# logic_board.net
KiCad netlist of a schematic drawn in EAGLE
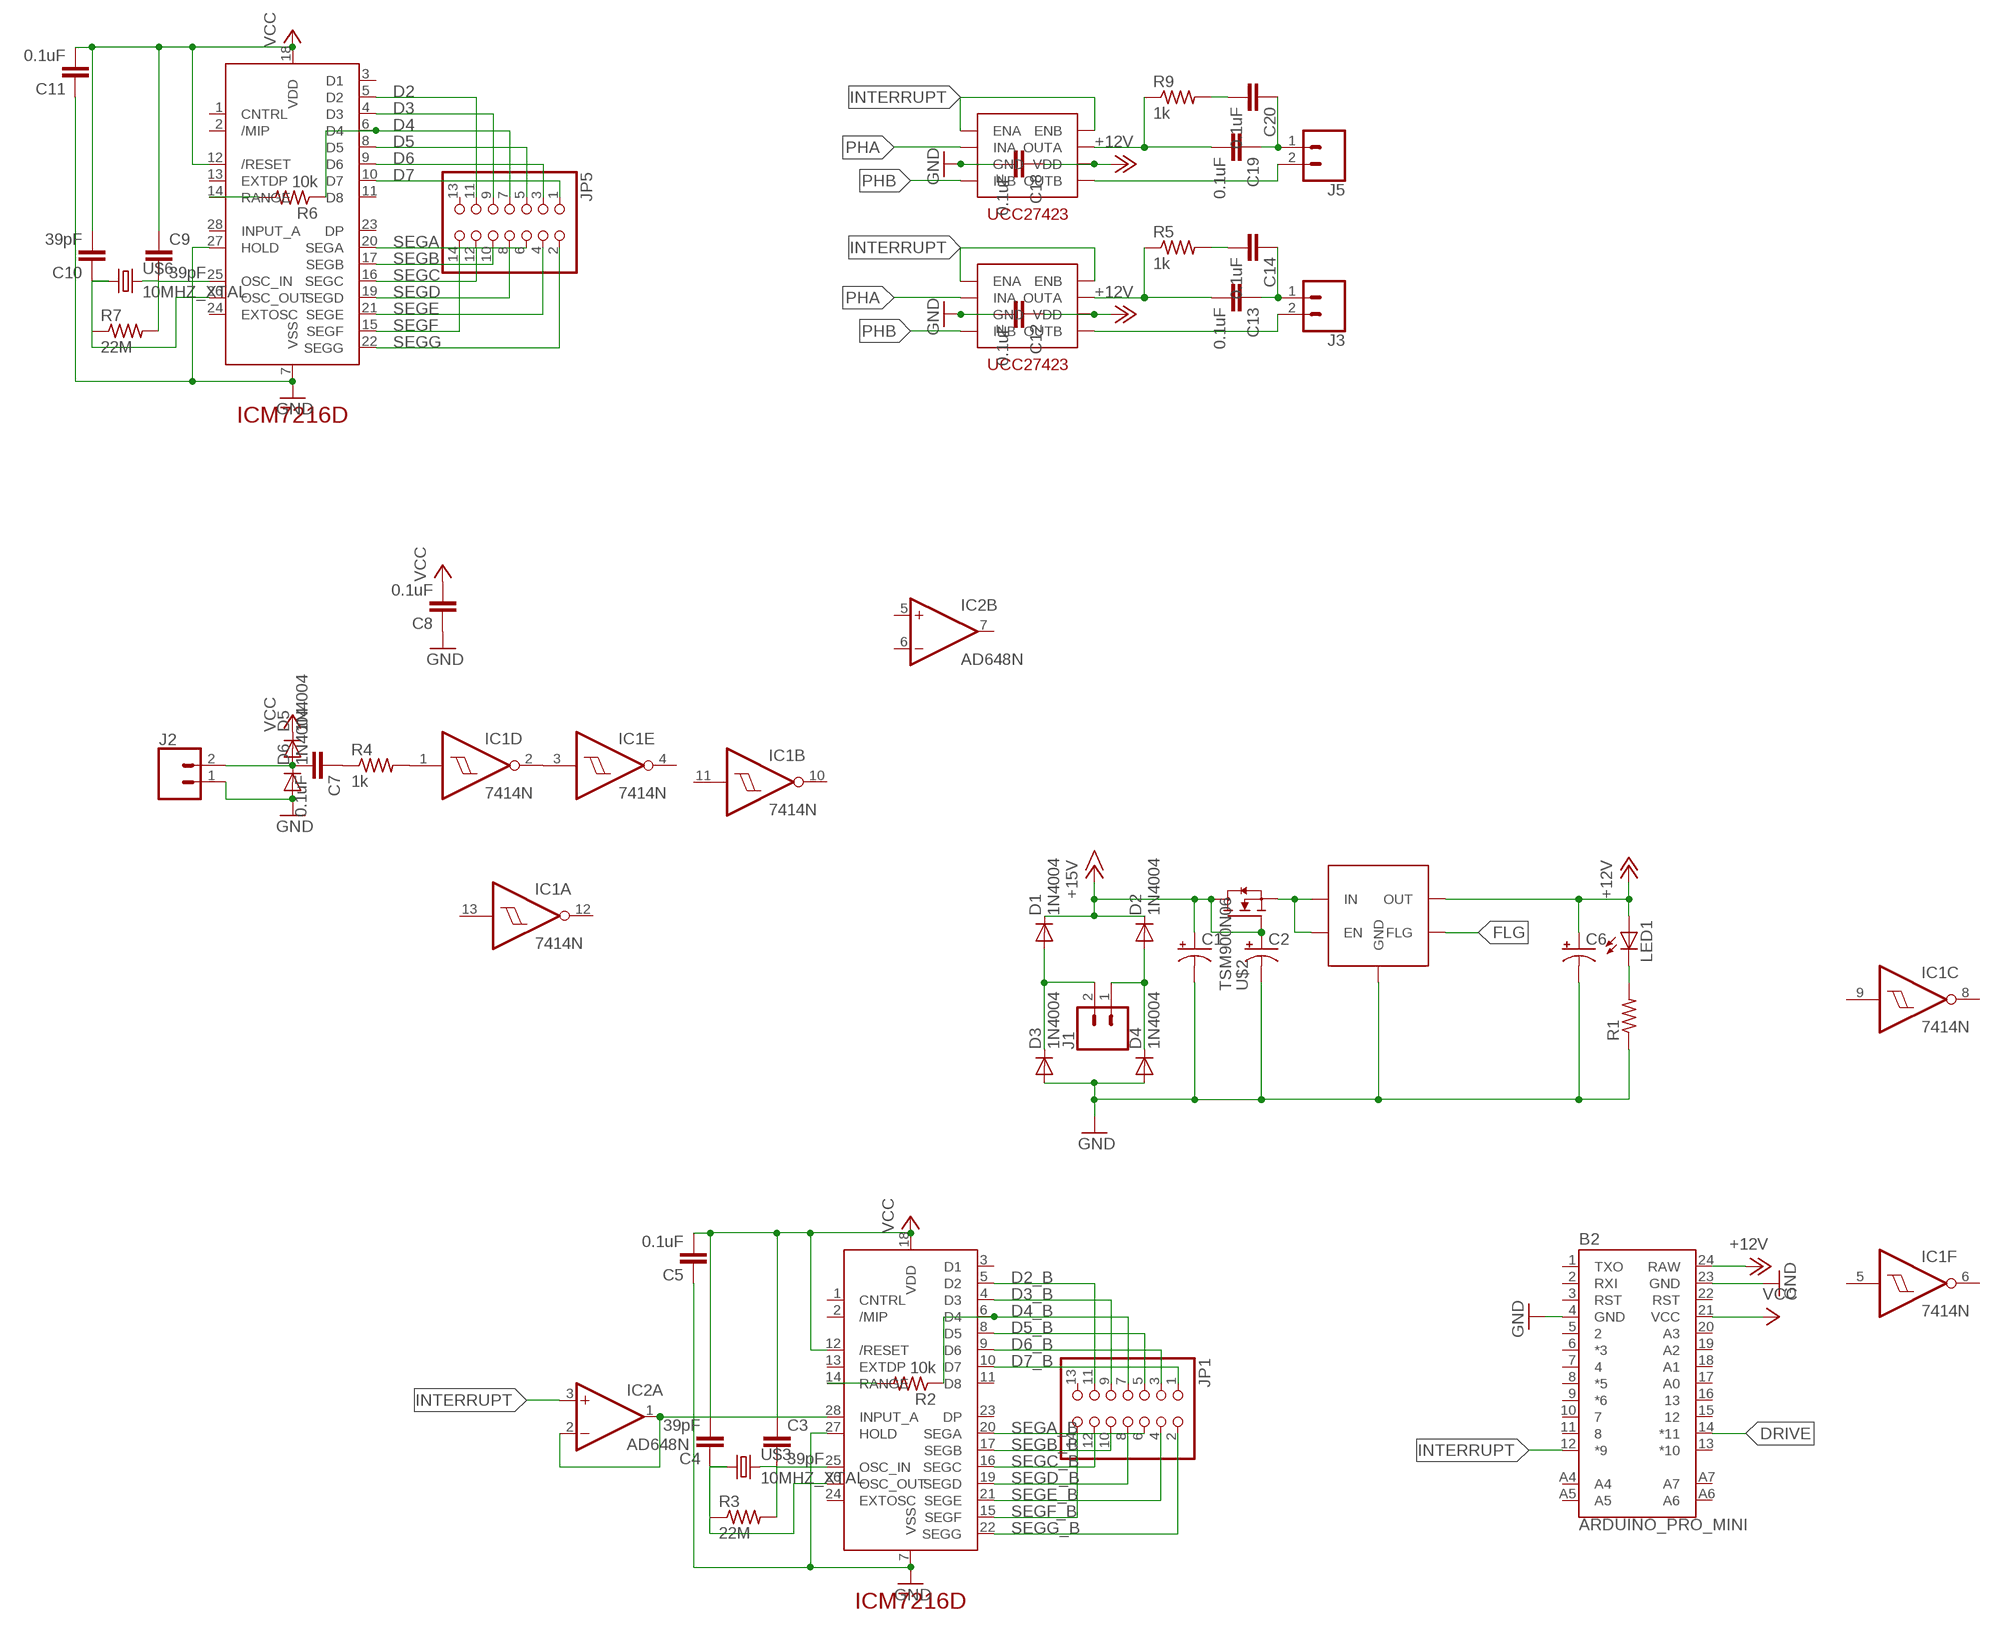
[diagram p0: schematic, sheet 1]

(export (version "E")
  (design (tool "Eeschema 10.0.6"))
  (components
    (comp (ref "B2")
      (value "ARDUINO_PRO_MINI")
      (footprint "eagle-import:ARDUINO_PRO_MINI")
      (libsource (lib "eagle-import") (part "ARDUINO_PRO_MINI"))
    )
    (comp (ref "C1")
      (value "CPOL-USE7.5-16")
      (footprint "eagle-import:E7,5-16")
      (libsource (lib "eagle-import") (part "CPOL-USE7.5-16"))
    )
    (comp (ref "C2")
      (value "CPOL-USE7.5-16")
      (footprint "eagle-import:E7,5-16")
      (libsource (lib "eagle-import") (part "CPOL-USE7.5-16"))
    )
    (comp (ref "C3")
      (value "39pF")
      (footprint "eagle-import:C050-030X075")
      (libsource (lib "eagle-import") (part "C-EU050-030X075"))
    )
    (comp (ref "C4")
      (value "39pF")
      (footprint "eagle-import:C050-030X075")
      (libsource (lib "eagle-import") (part "C-EU050-030X075"))
    )
    (comp (ref "C5")
      (value "0.1uF")
      (footprint "eagle-import:C050-030X075")
      (libsource (lib "eagle-import") (part "C-EU050-030X075"))
    )
    (comp (ref "C6")
      (value "CPOL-USE7.5-16")
      (footprint "eagle-import:E7,5-16")
      (libsource (lib "eagle-import") (part "CPOL-USE7.5-16"))
    )
    (comp (ref "C7")
      (value "0.1uF")
      (footprint "eagle-import:C050-030X075")
      (libsource (lib "eagle-import") (part "C-EU050-030X075"))
    )
    (comp (ref "C8")
      (value "0.1uF")
      (footprint "eagle-import:C050-030X075")
      (libsource (lib "eagle-import") (part "C-EU050-030X075"))
    )
    (comp (ref "C9")
      (value "39pF")
      (footprint "eagle-import:C050-030X075")
      (libsource (lib "eagle-import") (part "C-EU050-030X075"))
    )
    (comp (ref "C10")
      (value "39pF")
      (footprint "eagle-import:C050-030X075")
      (libsource (lib "eagle-import") (part "C-EU050-030X075"))
    )
    (comp (ref "C11")
      (value "0.1uF")
      (footprint "eagle-import:C050-030X075")
      (libsource (lib "eagle-import") (part "C-EU050-030X075"))
    )
    (comp (ref "C12")
      (value "0.1uF")
      (footprint "eagle-import:C050-030X075")
      (libsource (lib "eagle-import") (part "C-EU050-030X075"))
    )
    (comp (ref "C13")
      (value "0.1uF")
      (footprint "eagle-import:C050-030X075")
      (libsource (lib "eagle-import") (part "C-EU050-030X075"))
    )
    (comp (ref "C14")
      (value "0.1uF")
      (footprint "eagle-import:C050-030X075")
      (libsource (lib "eagle-import") (part "C-EU050-030X075"))
    )
    (comp (ref "C18")
      (value "0.1uF")
      (footprint "eagle-import:C050-030X075")
      (libsource (lib "eagle-import") (part "C-EU050-030X075"))
    )
    (comp (ref "C19")
      (value "0.1uF")
      (footprint "eagle-import:C050-030X075")
      (libsource (lib "eagle-import") (part "C-EU050-030X075"))
    )
    (comp (ref "C20")
      (value "0.1uF")
      (footprint "eagle-import:C050-030X075")
      (libsource (lib "eagle-import") (part "C-EU050-030X075"))
    )
    (comp (ref "D1")
      (value "1N4004")
      (footprint "eagle-import:DO41-10")
      (libsource (lib "eagle-import") (part "1N4004"))
    )
    (comp (ref "D2")
      (value "1N4004")
      (footprint "eagle-import:DO41-10")
      (libsource (lib "eagle-import") (part "1N4004"))
    )
    (comp (ref "D3")
      (value "1N4004")
      (footprint "eagle-import:DO41-10")
      (libsource (lib "eagle-import") (part "1N4004"))
    )
    (comp (ref "D4")
      (value "1N4004")
      (footprint "eagle-import:DO41-10")
      (libsource (lib "eagle-import") (part "1N4004"))
    )
    (comp (ref "D5")
      (value "1N4004")
      (footprint "eagle-import:DO41-10")
      (libsource (lib "eagle-import") (part "1N4004"))
    )
    (comp (ref "D6")
      (value "1N4004")
      (footprint "eagle-import:DO41-10")
      (libsource (lib "eagle-import") (part "1N4004"))
    )
    (comp (ref "IC1")
      (value "7414N")
      (footprint "eagle-import:DIL14")
      (libsource (lib "eagle-import") (part "7414N"))
    )
    (comp (ref "IC2")
      (value "AD648N")
      (footprint "eagle-import:DIL08")
      (libsource (lib "eagle-import") (part "AD648N"))
    )
    (comp (ref "J1")
      (value "CONN_025MM")
      (footprint "eagle-import:SCREWTERMINAL-5MM-2")
      (libsource (lib "eagle-import") (part "CONN_025MM"))
    )
    (comp (ref "J2")
      (value "CONN_025MM")
      (footprint "eagle-import:SCREWTERMINAL-5MM-2")
      (libsource (lib "eagle-import") (part "CONN_025MM"))
    )
    (comp (ref "J3")
      (value "CONN_025MM")
      (footprint "eagle-import:SCREWTERMINAL-5MM-2")
      (libsource (lib "eagle-import") (part "CONN_025MM"))
    )
    (comp (ref "J5")
      (value "CONN_025MM")
      (footprint "eagle-import:SCREWTERMINAL-5MM-2")
      (libsource (lib "eagle-import") (part "CONN_025MM"))
    )
    (comp (ref "JP1")
      (value "PINHD-2X7")
      (footprint "eagle-import:2X07")
      (libsource (lib "eagle-import") (part "PINHD-2X7"))
    )
    (comp (ref "JP5")
      (value "PINHD-2X7")
      (footprint "eagle-import:2X07")
      (libsource (lib "eagle-import") (part "PINHD-2X7"))
    )
    (comp (ref "LED1")
      (value "LED5MM")
      (footprint "eagle-import:LED5MM")
      (libsource (lib "eagle-import") (part "LED5MM"))
    )
    (comp (ref "R1")
      (value "R-US_0204/7")
      (footprint "eagle-import:0204_7")
      (libsource (lib "eagle-import") (part "R-US_0204/7"))
    )
    (comp (ref "R2")
      (value "10k")
      (footprint "eagle-import:0204_7")
      (libsource (lib "eagle-import") (part "R-US_0204/7"))
    )
    (comp (ref "R3")
      (value "22M")
      (footprint "eagle-import:0204_7")
      (libsource (lib "eagle-import") (part "R-US_0204/7"))
    )
    (comp (ref "R4")
      (value "1k")
      (footprint "eagle-import:0204_7")
      (libsource (lib "eagle-import") (part "R-US_0204/7"))
    )
    (comp (ref "R5")
      (value "1k")
      (footprint "eagle-import:0204_7")
      (libsource (lib "eagle-import") (part "R-US_0204/7"))
    )
    (comp (ref "R6")
      (value "10k")
      (footprint "eagle-import:0204_7")
      (libsource (lib "eagle-import") (part "R-US_0204/7"))
    )
    (comp (ref "R7")
      (value "22M")
      (footprint "eagle-import:0204_7")
      (libsource (lib "eagle-import") (part "R-US_0204/7"))
    )
    (comp (ref "R9")
      (value "1k")
      (footprint "eagle-import:0204_7")
      (libsource (lib "eagle-import") (part "R-US_0204/7"))
    )
    (comp (ref "U$1")
      (value "ICM7216D")
      (footprint "eagle-import:DIP1524W55P254L3740H635Q28B")
      (libsource (lib "eagle-import") (part "ICM7216D"))
    )
    (comp (ref "U$2")
      (value "TSM900N06")
      (footprint "eagle-import:TO-251S")
      (libsource (lib "eagle-import") (part "TSM900N06"))
    )
    (comp (ref "U$3")
      (value "10MHZ_XTAL")
      (footprint "eagle-import:XTAL")
      (libsource (lib "eagle-import") (part "10MHZ_XTAL"))
    )
    (comp (ref "U$4")
      (value "MIC29301")
      (footprint "eagle-import:TO-220")
      (libsource (lib "eagle-import") (part "MIC29301"))
    )
    (comp (ref "U$5")
      (value "ICM7216D")
      (footprint "eagle-import:DIP1524W55P254L3740H635Q28B")
      (libsource (lib "eagle-import") (part "ICM7216D"))
    )
    (comp (ref "U$6")
      (value "10MHZ_XTAL")
      (footprint "eagle-import:XTAL")
      (libsource (lib "eagle-import") (part "10MHZ_XTAL"))
    )
    (comp (ref "U$7")
      (value "UCC27423")
      (footprint "eagle-import:DIP762W53P254L959H508Q8B")
      (libsource (lib "eagle-import") (part "UCC27423"))
    )
    (comp (ref "U$9")
      (value "UCC27423")
      (footprint "eagle-import:DIP762W53P254L959H508Q8B")
      (libsource (lib "eagle-import") (part "UCC27423"))
    )
  )
  (nets
    (net (code "1") (name "+12V") (class "Default")
      (node (ref "B2") (pin "24") (pinfunction "RAW_24") (pintype "power_in"))
      (node (ref "C12") (pin "1") (pinfunction "1_1") (pintype "passive"))
      (node (ref "C18") (pin "1") (pinfunction "1_1") (pintype "passive"))
      (node (ref "C6") (pin "+") (pinfunction "+_+") (pintype "passive"))
      (node (ref "LED1") (pin "A") (pinfunction "A_A") (pintype "passive"))
      (node (ref "U$4") (pin "P$4") (pinfunction "OUT_P$4") (pintype "bidirectional"))
      (node (ref "U$7") (pin "6") (pinfunction "VDD_6") (pintype "bidirectional"))
      (node (ref "U$9") (pin "6") (pinfunction "VDD_6") (pintype "bidirectional"))
    )
    (net (code "2") (name "+15V") (class "Default")
      (node (ref "C1") (pin "+") (pinfunction "+_+") (pintype "passive"))
      (node (ref "C2") (pin "+") (pinfunction "+_+") (pintype "passive"))
      (node (ref "D1") (pin "C") (pinfunction "C_C") (pintype "passive"))
      (node (ref "D2") (pin "C") (pinfunction "C_C") (pintype "passive"))
      (node (ref "U$2") (pin "P$1") (pinfunction "G_P$1") (pintype "passive"))
      (node (ref "U$2") (pin "P$2") (pinfunction "D_P$2") (pintype "passive"))
    )
    (net (code "3") (name "/D2") (class "Default")
      (node (ref "JP5") (pin "11") (pinfunction "11_11") (pintype "passive"))
      (node (ref "U$5") (pin "5") (pinfunction "D2_5") (pintype "bidirectional"))
    )
    (net (code "4") (name "/D2_B") (class "Default")
      (node (ref "JP1") (pin "11") (pinfunction "11_11") (pintype "passive"))
      (node (ref "U$1") (pin "5") (pinfunction "D2_5") (pintype "bidirectional"))
    )
    (net (code "5") (name "/D3") (class "Default")
      (node (ref "JP5") (pin "9") (pinfunction "9_9") (pintype "passive"))
      (node (ref "U$5") (pin "4") (pinfunction "D3_4") (pintype "bidirectional"))
    )
    (net (code "6") (name "/D3_B") (class "Default")
      (node (ref "JP1") (pin "9") (pinfunction "9_9") (pintype "passive"))
      (node (ref "U$1") (pin "4") (pinfunction "D3_4") (pintype "bidirectional"))
    )
    (net (code "7") (name "/D4") (class "Default")
      (node (ref "JP5") (pin "7") (pinfunction "7_7") (pintype "passive"))
      (node (ref "R6") (pin "1") (pinfunction "1_1") (pintype "passive"))
      (node (ref "U$5") (pin "6") (pinfunction "D4_6") (pintype "bidirectional"))
    )
    (net (code "8") (name "/D4_B") (class "Default")
      (node (ref "JP1") (pin "7") (pinfunction "7_7") (pintype "passive"))
      (node (ref "R2") (pin "1") (pinfunction "1_1") (pintype "passive"))
      (node (ref "U$1") (pin "6") (pinfunction "D4_6") (pintype "bidirectional"))
    )
    (net (code "9") (name "/D5") (class "Default")
      (node (ref "JP5") (pin "5") (pinfunction "5_5") (pintype "passive"))
      (node (ref "U$5") (pin "8") (pinfunction "D5_8") (pintype "bidirectional"))
    )
    (net (code "10") (name "/D5_B") (class "Default")
      (node (ref "JP1") (pin "5") (pinfunction "5_5") (pintype "passive"))
      (node (ref "U$1") (pin "8") (pinfunction "D5_8") (pintype "bidirectional"))
    )
    (net (code "11") (name "/D6") (class "Default")
      (node (ref "JP5") (pin "3") (pinfunction "3_3") (pintype "passive"))
      (node (ref "U$5") (pin "9") (pinfunction "D6_9") (pintype "bidirectional"))
    )
    (net (code "12") (name "/D6_B") (class "Default")
      (node (ref "JP1") (pin "3") (pinfunction "3_3") (pintype "passive"))
      (node (ref "U$1") (pin "9") (pinfunction "D6_9") (pintype "bidirectional"))
    )
    (net (code "13") (name "/D7") (class "Default")
      (node (ref "JP5") (pin "1") (pinfunction "1_1") (pintype "passive"))
      (node (ref "U$5") (pin "10") (pinfunction "D7_10") (pintype "bidirectional"))
    )
    (net (code "14") (name "/D7_B") (class "Default")
      (node (ref "JP1") (pin "1") (pinfunction "1_1") (pintype "passive"))
      (node (ref "U$1") (pin "10") (pinfunction "D7_10") (pintype "bidirectional"))
    )
    (net (code "15") (name "/SEGA") (class "Default")
      (node (ref "JP5") (pin "6") (pinfunction "6_6") (pintype "passive"))
      (node (ref "U$5") (pin "20") (pinfunction "SEGA_20") (pintype "bidirectional"))
    )
    (net (code "16") (name "/SEGA_B") (class "Default")
      (node (ref "JP1") (pin "6") (pinfunction "6_6") (pintype "passive"))
      (node (ref "U$1") (pin "20") (pinfunction "SEGA_20") (pintype "bidirectional"))
    )
    (net (code "17") (name "/SEGB") (class "Default")
      (node (ref "JP5") (pin "10") (pinfunction "10_10") (pintype "passive"))
      (node (ref "U$5") (pin "17") (pinfunction "SEGB_17") (pintype "bidirectional"))
    )
    (net (code "18") (name "/SEGB_B") (class "Default")
      (node (ref "JP1") (pin "10") (pinfunction "10_10") (pintype "passive"))
      (node (ref "U$1") (pin "17") (pinfunction "SEGB_17") (pintype "bidirectional"))
    )
    (net (code "19") (name "/SEGC") (class "Default")
      (node (ref "JP5") (pin "12") (pinfunction "12_12") (pintype "passive"))
      (node (ref "U$5") (pin "16") (pinfunction "SEGC_16") (pintype "bidirectional"))
    )
    (net (code "20") (name "/SEGC_B") (class "Default")
      (node (ref "JP1") (pin "12") (pinfunction "12_12") (pintype "passive"))
      (node (ref "U$1") (pin "16") (pinfunction "SEGC_16") (pintype "bidirectional"))
    )
    (net (code "21") (name "/SEGD") (class "Default")
      (node (ref "JP5") (pin "8") (pinfunction "8_8") (pintype "passive"))
      (node (ref "U$5") (pin "19") (pinfunction "SEGD_19") (pintype "bidirectional"))
    )
    (net (code "22") (name "/SEGD_B") (class "Default")
      (node (ref "JP1") (pin "8") (pinfunction "8_8") (pintype "passive"))
      (node (ref "U$1") (pin "19") (pinfunction "SEGD_19") (pintype "bidirectional"))
    )
    (net (code "23") (name "/SEGE") (class "Default")
      (node (ref "JP5") (pin "4") (pinfunction "4_4") (pintype "passive"))
      (node (ref "U$5") (pin "21") (pinfunction "SEGE_21") (pintype "bidirectional"))
    )
    (net (code "24") (name "/SEGE_B") (class "Default")
      (node (ref "JP1") (pin "4") (pinfunction "4_4") (pintype "passive"))
      (node (ref "U$1") (pin "21") (pinfunction "SEGE_21") (pintype "bidirectional"))
    )
    (net (code "25") (name "/SEGF") (class "Default")
      (node (ref "JP5") (pin "14") (pinfunction "14_14") (pintype "passive"))
      (node (ref "U$5") (pin "15") (pinfunction "SEGF_15") (pintype "bidirectional"))
    )
    (net (code "26") (name "/SEGF_B") (class "Default")
      (node (ref "JP1") (pin "14") (pinfunction "14_14") (pintype "passive"))
      (node (ref "U$1") (pin "15") (pinfunction "SEGF_15") (pintype "bidirectional"))
    )
    (net (code "27") (name "/SEGG") (class "Default")
      (node (ref "JP5") (pin "2") (pinfunction "2_2") (pintype "passive"))
      (node (ref "U$5") (pin "22") (pinfunction "SEGG_22") (pintype "bidirectional"))
    )
    (net (code "28") (name "/SEGG_B") (class "Default")
      (node (ref "JP1") (pin "2") (pinfunction "2_2") (pintype "passive"))
      (node (ref "U$1") (pin "22") (pinfunction "SEGG_22") (pintype "bidirectional"))
    )
    (net (code "29") (name "DRIVE") (class "Default")
      (node (ref "B2") (pin "14") (pinfunction "*11_14") (pintype "bidirectional"))
    )
    (net (code "30") (name "FLG") (class "Default")
      (node (ref "U$4") (pin "P$5") (pinfunction "FLG_P$5") (pintype "bidirectional"))
    )
    (net (code "31") (name "GND") (class "Default")
      (node (ref "B2") (pin "23") (pinfunction "GND_23") (pintype "power_in"))
      (node (ref "B2") (pin "4") (pinfunction "GND_4") (pintype "power_in"))
      (node (ref "C1") (pin "-") (pinfunction "-_-") (pintype "passive"))
      (node (ref "C11") (pin "1") (pinfunction "1_1") (pintype "passive"))
      (node (ref "C12") (pin "2") (pinfunction "2_2") (pintype "passive"))
      (node (ref "C18") (pin "2") (pinfunction "2_2") (pintype "passive"))
      (node (ref "C2") (pin "-") (pinfunction "-_-") (pintype "passive"))
      (node (ref "C5") (pin "1") (pinfunction "1_1") (pintype "passive"))
      (node (ref "C6") (pin "-") (pinfunction "-_-") (pintype "passive"))
      (node (ref "C8") (pin "1") (pinfunction "1_1") (pintype "passive"))
      (node (ref "D3") (pin "A") (pinfunction "A_A") (pintype "passive"))
      (node (ref "D4") (pin "A") (pinfunction "A_A") (pintype "passive"))
      (node (ref "D6") (pin "A") (pinfunction "A_A") (pintype "passive"))
      (node (ref "J2") (pin "1") (pinfunction "1_1") (pintype "passive"))
      (node (ref "R1") (pin "1") (pinfunction "1_1") (pintype "passive"))
      (node (ref "U$1") (pin "27") (pinfunction "HOLD_27") (pintype "bidirectional"))
      (node (ref "U$1") (pin "7") (pinfunction "VSS_7") (pintype "bidirectional"))
      (node (ref "U$4") (pin "P$3") (pinfunction "GND_P$3") (pintype "bidirectional"))
      (node (ref "U$5") (pin "27") (pinfunction "HOLD_27") (pintype "bidirectional"))
      (node (ref "U$5") (pin "7") (pinfunction "VSS_7") (pintype "bidirectional"))
      (node (ref "U$7") (pin "3") (pinfunction "GND_3") (pintype "bidirectional"))
      (node (ref "U$9") (pin "3") (pinfunction "GND_3") (pintype "bidirectional"))
    )
    (net (code "32") (name "INTERRUPT") (class "Default")
      (node (ref "B2") (pin "12") (pinfunction "*9_12") (pintype "bidirectional"))
      (node (ref "IC2") (pin "3") (pinfunction "+IN_3") (pintype "input"))
      (node (ref "U$7") (pin "1") (pinfunction "ENA_1") (pintype "bidirectional"))
      (node (ref "U$7") (pin "8") (pinfunction "ENB_8") (pintype "bidirectional"))
      (node (ref "U$9") (pin "1") (pinfunction "ENA_1") (pintype "bidirectional"))
      (node (ref "U$9") (pin "8") (pinfunction "ENB_8") (pintype "bidirectional"))
    )
    (net (code "33") (name "Net-(C7-Pad1)") (class "Default")
      (node (ref "C7") (pin "1") (pinfunction "1_1") (pintype "passive"))
      (node (ref "R4") (pin "1") (pinfunction "1_1") (pintype "passive"))
    )
    (net (code "34") (name "Net-(C7-Pad2)") (class "Default")
      (node (ref "C7") (pin "2") (pinfunction "2_2") (pintype "passive"))
      (node (ref "D5") (pin "A") (pinfunction "A_A") (pintype "passive"))
      (node (ref "D6") (pin "C") (pinfunction "C_C") (pintype "passive"))
      (node (ref "J2") (pin "2") (pinfunction "2_2") (pintype "passive"))
    )
    (net (code "35") (name "Net-(C13-Pad1)") (class "Default")
      (node (ref "C13") (pin "1") (pinfunction "1_1") (pintype "passive"))
      (node (ref "C14") (pin "1") (pinfunction "1_1") (pintype "passive"))
      (node (ref "J3") (pin "1") (pinfunction "1_1") (pintype "passive"))
    )
    (net (code "36") (name "Net-(C14-Pad2)") (class "Default")
      (node (ref "C14") (pin "2") (pinfunction "2_2") (pintype "passive"))
      (node (ref "R5") (pin "2") (pinfunction "2_2") (pintype "passive"))
    )
    (net (code "37") (name "Net-(C19-Pad1)") (class "Default")
      (node (ref "C19") (pin "1") (pinfunction "1_1") (pintype "passive"))
      (node (ref "C20") (pin "1") (pinfunction "1_1") (pintype "passive"))
      (node (ref "J5") (pin "1") (pinfunction "1_1") (pintype "passive"))
    )
    (net (code "38") (name "Net-(C20-Pad2)") (class "Default")
      (node (ref "C20") (pin "2") (pinfunction "2_2") (pintype "passive"))
      (node (ref "R9") (pin "2") (pinfunction "2_2") (pintype "passive"))
    )
    (net (code "39") (name "Net-(D1-PadA)") (class "Default")
      (node (ref "D1") (pin "A") (pinfunction "A_A") (pintype "passive"))
      (node (ref "D3") (pin "C") (pinfunction "C_C") (pintype "passive"))
      (node (ref "J1") (pin "2") (pinfunction "2_2") (pintype "passive"))
    )
    (net (code "40") (name "Net-(D2-PadA)") (class "Default")
      (node (ref "D2") (pin "A") (pinfunction "A_A") (pintype "passive"))
      (node (ref "D4") (pin "C") (pinfunction "C_C") (pintype "passive"))
      (node (ref "J1") (pin "1") (pinfunction "1_1") (pintype "passive"))
    )
    (net (code "41") (name "Net-(IC1D-I)") (class "Default")
      (node (ref "IC1") (pin "1") (pinfunction "I_1") (pintype "input"))
      (node (ref "R4") (pin "2") (pinfunction "2_2") (pintype "passive"))
    )
    (net (code "42") (name "Net-(IC1D-O)") (class "Default")
      (node (ref "IC1") (pin "2") (pinfunction "O_2") (pintype "output"))
      (node (ref "IC1") (pin "3") (pinfunction "I_3") (pintype "input"))
    )
    (net (code "43") (name "Net-(IC2A--IN)") (class "Default")
      (node (ref "IC2") (pin "1") (pinfunction "OUT_1") (pintype "output"))
      (node (ref "IC2") (pin "2") (pinfunction "-IN_2") (pintype "input"))
      (node (ref "U$1") (pin "28") (pinfunction "INPUT_A_28") (pintype "bidirectional"))
    )
    (net (code "44") (name "Net-(LED1-C)") (class "Default")
      (node (ref "LED1") (pin "K") (pinfunction "C_K") (pintype "passive"))
      (node (ref "R1") (pin "2") (pinfunction "2_2") (pintype "passive"))
    )
    (net (code "45") (name "Net-(U$1-OSC_IN)") (class "Default")
      (node (ref "C3") (pin "2") (pinfunction "2_2") (pintype "passive"))
      (node (ref "R3") (pin "2") (pinfunction "2_2") (pintype "passive"))
      (node (ref "U$1") (pin "25") (pinfunction "OSC_IN_25") (pintype "bidirectional"))
      (node (ref "U$3") (pin "P$2") (pinfunction "2_P$2") (pintype "passive"))
    )
    (net (code "46") (name "Net-(U$1-OSC_OUT)") (class "Default")
      (node (ref "C4") (pin "1") (pinfunction "1_1") (pintype "passive"))
      (node (ref "R3") (pin "1") (pinfunction "1_1") (pintype "passive"))
      (node (ref "U$1") (pin "26") (pinfunction "OSC_OUT_26") (pintype "bidirectional"))
      (node (ref "U$3") (pin "P$1") (pinfunction "1_P$1") (pintype "passive"))
    )
    (net (code "47") (name "Net-(U$1-RANGE)") (class "Default")
      (node (ref "R2") (pin "2") (pinfunction "2_2") (pintype "passive"))
      (node (ref "U$1") (pin "14") (pinfunction "RANGE_14") (pintype "bidirectional"))
    )
    (net (code "48") (name "Net-(U$2-S)") (class "Default")
      (node (ref "U$2") (pin "P$3") (pinfunction "S_P$3") (pintype "passive"))
      (node (ref "U$4") (pin "P$1") (pinfunction "EN_P$1") (pintype "bidirectional"))
      (node (ref "U$4") (pin "P$2") (pinfunction "IN_P$2") (pintype "bidirectional"))
    )
    (net (code "49") (name "Net-(U$5-OSC_IN)") (class "Default")
      (node (ref "C9") (pin "2") (pinfunction "2_2") (pintype "passive"))
      (node (ref "R7") (pin "2") (pinfunction "2_2") (pintype "passive"))
      (node (ref "U$5") (pin "25") (pinfunction "OSC_IN_25") (pintype "bidirectional"))
      (node (ref "U$6") (pin "P$2") (pinfunction "2_P$2") (pintype "passive"))
    )
    (net (code "50") (name "Net-(U$5-OSC_OUT)") (class "Default")
      (node (ref "C10") (pin "1") (pinfunction "1_1") (pintype "passive"))
      (node (ref "R7") (pin "1") (pinfunction "1_1") (pintype "passive"))
      (node (ref "U$5") (pin "26") (pinfunction "OSC_OUT_26") (pintype "bidirectional"))
      (node (ref "U$6") (pin "P$1") (pinfunction "1_P$1") (pintype "passive"))
    )
    (net (code "51") (name "Net-(U$5-RANGE)") (class "Default")
      (node (ref "R6") (pin "2") (pinfunction "2_2") (pintype "passive"))
      (node (ref "U$5") (pin "14") (pinfunction "RANGE_14") (pintype "bidirectional"))
    )
    (net (code "52") (name "Net-(U$7-OUTA)") (class "Default")
      (node (ref "C13") (pin "2") (pinfunction "2_2") (pintype "passive"))
      (node (ref "R5") (pin "1") (pinfunction "1_1") (pintype "passive"))
      (node (ref "U$7") (pin "7") (pinfunction "OUTA_7") (pintype "bidirectional"))
    )
    (net (code "53") (name "Net-(U$7-OUTB)") (class "Default")
      (node (ref "J3") (pin "2") (pinfunction "2_2") (pintype "passive"))
      (node (ref "U$7") (pin "5") (pinfunction "OUTB_5") (pintype "bidirectional"))
    )
    (net (code "54") (name "Net-(U$9-OUTA)") (class "Default")
      (node (ref "C19") (pin "2") (pinfunction "2_2") (pintype "passive"))
      (node (ref "R9") (pin "1") (pinfunction "1_1") (pintype "passive"))
      (node (ref "U$9") (pin "7") (pinfunction "OUTA_7") (pintype "bidirectional"))
    )
    (net (code "55") (name "Net-(U$9-OUTB)") (class "Default")
      (node (ref "J5") (pin "2") (pinfunction "2_2") (pintype "passive"))
      (node (ref "U$9") (pin "5") (pinfunction "OUTB_5") (pintype "bidirectional"))
    )
    (net (code "56") (name "PHA") (class "Default")
      (node (ref "U$7") (pin "2") (pinfunction "INA_2") (pintype "bidirectional"))
      (node (ref "U$9") (pin "2") (pinfunction "INA_2") (pintype "bidirectional"))
    )
    (net (code "57") (name "PHB") (class "Default")
      (node (ref "U$7") (pin "4") (pinfunction "INB_4") (pintype "bidirectional"))
      (node (ref "U$9") (pin "4") (pinfunction "INB_4") (pintype "bidirectional"))
    )
    (net (code "58") (name "VCC") (class "Default")
      (node (ref "B2") (pin "21") (pinfunction "VCC_21") (pintype "power_in"))
      (node (ref "C10") (pin "2") (pinfunction "2_2") (pintype "passive"))
      (node (ref "C11") (pin "2") (pinfunction "2_2") (pintype "passive"))
      (node (ref "C3") (pin "1") (pinfunction "1_1") (pintype "passive"))
      (node (ref "C4") (pin "2") (pinfunction "2_2") (pintype "passive"))
      (node (ref "C5") (pin "2") (pinfunction "2_2") (pintype "passive"))
      (node (ref "C8") (pin "2") (pinfunction "2_2") (pintype "passive"))
      (node (ref "C9") (pin "1") (pinfunction "1_1") (pintype "passive"))
      (node (ref "D5") (pin "C") (pinfunction "C_C") (pintype "passive"))
      (node (ref "U$1") (pin "12") (pinfunction "/RESET_12") (pintype "bidirectional"))
      (node (ref "U$1") (pin "18") (pinfunction "VDD_18") (pintype "bidirectional"))
      (node (ref "U$5") (pin "12") (pinfunction "/RESET_12") (pintype "bidirectional"))
      (node (ref "U$5") (pin "18") (pinfunction "VDD_18") (pintype "bidirectional"))
    )
    (net (code "59") (name "unconnected-(B2-*3-Pad6)") (class "Default")
      (node (ref "B2") (pin "6") (pinfunction "*3_6") (pintype "bidirectional"))
    )
    (net (code "60") (name "unconnected-(B2-*5-Pad8)") (class "Default")
      (node (ref "B2") (pin "8") (pinfunction "*5_8") (pintype "bidirectional"))
    )
    (net (code "61") (name "unconnected-(B2-*6-Pad9)") (class "Default")
      (node (ref "B2") (pin "9") (pinfunction "*6_9") (pintype "bidirectional"))
    )
    (net (code "62") (name "unconnected-(B2-*10-Pad13)") (class "Default")
      (node (ref "B2") (pin "13") (pinfunction "*10_13") (pintype "bidirectional"))
    )
    (net (code "63") (name "unconnected-(B2-2-Pad5)") (class "Default")
      (node (ref "B2") (pin "5") (pinfunction "2_5") (pintype "bidirectional"))
    )
    (net (code "64") (name "unconnected-(B2-4-Pad7)") (class "Default")
      (node (ref "B2") (pin "7") (pinfunction "4_7") (pintype "bidirectional"))
    )
    (net (code "65") (name "unconnected-(B2-7-Pad10)") (class "Default")
      (node (ref "B2") (pin "10") (pinfunction "7_10") (pintype "bidirectional"))
    )
    (net (code "66") (name "unconnected-(B2-8-Pad11)") (class "Default")
      (node (ref "B2") (pin "11") (pinfunction "8_11") (pintype "bidirectional"))
    )
    (net (code "67") (name "unconnected-(B2-12-Pad15)") (class "Default")
      (node (ref "B2") (pin "15") (pinfunction "12_15") (pintype "bidirectional"))
    )
    (net (code "68") (name "unconnected-(B2-13-Pad16)") (class "Default")
      (node (ref "B2") (pin "16") (pinfunction "13_16") (pintype "bidirectional"))
    )
    (net (code "69") (name "unconnected-(B2-A0-Pad17)") (class "Default")
      (node (ref "B2") (pin "17") (pinfunction "A0_17") (pintype "bidirectional"))
    )
    (net (code "70") (name "unconnected-(B2-A1-Pad18)") (class "Default")
      (node (ref "B2") (pin "18") (pinfunction "A1_18") (pintype "bidirectional"))
    )
    (net (code "71") (name "unconnected-(B2-A2-Pad19)") (class "Default")
      (node (ref "B2") (pin "19") (pinfunction "A2_19") (pintype "bidirectional"))
    )
    (net (code "72") (name "unconnected-(B2-A3-Pad20)") (class "Default")
      (node (ref "B2") (pin "20") (pinfunction "A3_20") (pintype "bidirectional"))
    )
    (net (code "73") (name "unconnected-(B2-PadA4)") (class "Default")
      (node (ref "B2") (pin "A4") (pinfunction "A4_A4") (pintype "bidirectional"))
    )
    (net (code "74") (name "unconnected-(B2-PadA5)") (class "Default")
      (node (ref "B2") (pin "A5") (pinfunction "A5_A5") (pintype "bidirectional"))
    )
    (net (code "75") (name "unconnected-(B2-PadA6)") (class "Default")
      (node (ref "B2") (pin "A6") (pinfunction "A6_A6") (pintype "bidirectional"))
    )
    (net (code "76") (name "unconnected-(B2-PadA7)") (class "Default")
      (node (ref "B2") (pin "A7") (pinfunction "A7_A7") (pintype "bidirectional"))
    )
    (net (code "77") (name "unconnected-(B2-RST-Pad3)") (class "Default")
      (node (ref "B2") (pin "3") (pinfunction "RST_3") (pintype "bidirectional"))
    )
    (net (code "78") (name "unconnected-(B2-RST-Pad22)") (class "Default")
      (node (ref "B2") (pin "22") (pinfunction "RST_22") (pintype "bidirectional"))
    )
    (net (code "79") (name "unconnected-(B2-RXI-Pad2)") (class "Default")
      (node (ref "B2") (pin "2") (pinfunction "RXI_2") (pintype "bidirectional"))
    )
    (net (code "80") (name "unconnected-(B2-TXO-Pad1)") (class "Default")
      (node (ref "B2") (pin "1") (pinfunction "TXO_1") (pintype "bidirectional"))
    )
    (net (code "81") (name "unconnected-(IC1A-I-Pad13)") (class "Default")
      (node (ref "IC1") (pin "13") (pinfunction "I_13") (pintype "input"))
    )
    (net (code "82") (name "unconnected-(IC1A-O-Pad12)") (class "Default")
      (node (ref "IC1") (pin "12") (pinfunction "O_12") (pintype "output"))
    )
    (net (code "83") (name "unconnected-(IC1B-I-Pad11)") (class "Default")
      (node (ref "IC1") (pin "11") (pinfunction "I_11") (pintype "input"))
    )
    (net (code "84") (name "unconnected-(IC1B-O-Pad10)") (class "Default")
      (node (ref "IC1") (pin "10") (pinfunction "O_10") (pintype "output"))
    )
    (net (code "85") (name "unconnected-(IC1C-I-Pad9)") (class "Default")
      (node (ref "IC1") (pin "9") (pinfunction "I_9") (pintype "input"))
    )
    (net (code "86") (name "unconnected-(IC1C-O-Pad8)") (class "Default")
      (node (ref "IC1") (pin "8") (pinfunction "O_8") (pintype "output"))
    )
    (net (code "87") (name "unconnected-(IC1E-O-Pad4)") (class "Default")
      (node (ref "IC1") (pin "4") (pinfunction "O_4") (pintype "output"))
    )
    (net (code "88") (name "unconnected-(IC1F-I-Pad5)") (class "Default")
      (node (ref "IC1") (pin "5") (pinfunction "I_5") (pintype "input"))
    )
    (net (code "89") (name "unconnected-(IC1F-O-Pad6)") (class "Default")
      (node (ref "IC1") (pin "6") (pinfunction "O_6") (pintype "output"))
    )
    (net (code "90") (name "unconnected-(IC2B-+IN-Pad5)") (class "Default")
      (node (ref "IC2") (pin "5") (pinfunction "+IN_5") (pintype "input"))
    )
    (net (code "91") (name "unconnected-(IC2B--IN-Pad6)") (class "Default")
      (node (ref "IC2") (pin "6") (pinfunction "-IN_6") (pintype "input"))
    )
    (net (code "92") (name "unconnected-(IC2B-OUT-Pad7)") (class "Default")
      (node (ref "IC2") (pin "7") (pinfunction "OUT_7") (pintype "output"))
    )
    (net (code "93") (name "unconnected-(JP1-Pad13)") (class "Default")
      (node (ref "JP1") (pin "13") (pinfunction "13_13") (pintype "passive"))
    )
    (net (code "94") (name "unconnected-(JP5-Pad13)") (class "Default")
      (node (ref "JP5") (pin "13") (pinfunction "13_13") (pintype "passive"))
    )
    (net (code "95") (name "unconnected-(U$1-CNTRL-Pad1)") (class "Default")
      (node (ref "U$1") (pin "1") (pinfunction "CNTRL_1") (pintype "bidirectional"))
    )
    (net (code "96") (name "unconnected-(U$1-D1-Pad3)") (class "Default")
      (node (ref "U$1") (pin "3") (pinfunction "D1_3") (pintype "bidirectional"))
    )
    (net (code "97") (name "unconnected-(U$1-D8-Pad11)") (class "Default")
      (node (ref "U$1") (pin "11") (pinfunction "D8_11") (pintype "bidirectional"))
    )
    (net (code "98") (name "unconnected-(U$1-DP-Pad23)") (class "Default")
      (node (ref "U$1") (pin "23") (pinfunction "DP_23") (pintype "bidirectional"))
    )
    (net (code "99") (name "unconnected-(U$1-EXTDP-Pad13)") (class "Default")
      (node (ref "U$1") (pin "13") (pinfunction "EXTDP_13") (pintype "bidirectional"))
    )
    (net (code "100") (name "unconnected-(U$1-EXTOSC-Pad24)") (class "Default")
      (node (ref "U$1") (pin "24") (pinfunction "EXTOSC_24") (pintype "bidirectional"))
    )
    (net (code "101") (name "unconnected-(U$1-{slash}MIP-Pad2)") (class "Default")
      (node (ref "U$1") (pin "2") (pinfunction "/MIP_2") (pintype "bidirectional"))
    )
    (net (code "102") (name "unconnected-(U$5-CNTRL-Pad1)") (class "Default")
      (node (ref "U$5") (pin "1") (pinfunction "CNTRL_1") (pintype "bidirectional"))
    )
    (net (code "103") (name "unconnected-(U$5-D1-Pad3)") (class "Default")
      (node (ref "U$5") (pin "3") (pinfunction "D1_3") (pintype "bidirectional"))
    )
    (net (code "104") (name "unconnected-(U$5-D8-Pad11)") (class "Default")
      (node (ref "U$5") (pin "11") (pinfunction "D8_11") (pintype "bidirectional"))
    )
    (net (code "105") (name "unconnected-(U$5-DP-Pad23)") (class "Default")
      (node (ref "U$5") (pin "23") (pinfunction "DP_23") (pintype "bidirectional"))
    )
    (net (code "106") (name "unconnected-(U$5-EXTDP-Pad13)") (class "Default")
      (node (ref "U$5") (pin "13") (pinfunction "EXTDP_13") (pintype "bidirectional"))
    )
    (net (code "107") (name "unconnected-(U$5-EXTOSC-Pad24)") (class "Default")
      (node (ref "U$5") (pin "24") (pinfunction "EXTOSC_24") (pintype "bidirectional"))
    )
    (net (code "108") (name "unconnected-(U$5-INPUT_A-Pad28)") (class "Default")
      (node (ref "U$5") (pin "28") (pinfunction "INPUT_A_28") (pintype "bidirectional"))
    )
    (net (code "109") (name "unconnected-(U$5-{slash}MIP-Pad2)") (class "Default")
      (node (ref "U$5") (pin "2") (pinfunction "/MIP_2") (pintype "bidirectional"))
    )
  )
)
